# Amphenol_ICC_1.net
KiCad netlist of a schematic drawn in Altium Designer
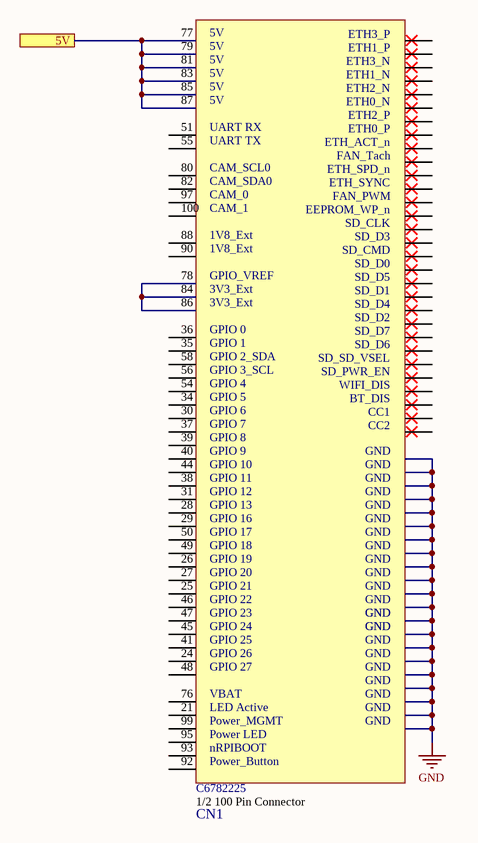
[diagram p0: Amphenol ICC_1.SchDoc]

(export (version "E")
  (design (tool "Eeschema 10.0.6"))
  (components
    (comp (ref "CN1")
      (value "1/2 100 Pin Connector")
      (footprint "CONN-SMD_100P-P0.40_10164227-1001A1RLF")
      (description "100 Position Board to Board Connector Surface Mount,P=0.4mm Gold")
      (fields (field (name "SOURCE") "LCSC"))
      (libsource (lib "C6782225_Part 1") (part "10164227-1001A1RLF"))
    )
  )
  (nets
    (net (code "1") (name "/5V") (class "Default")
      (node (ref "CN1") (pin "77") (pinfunction "77_77") (pintype "passive"))
      (node (ref "CN1") (pin "79") (pinfunction "79_79") (pintype "passive"))
      (node (ref "CN1") (pin "81") (pinfunction "81_81") (pintype "passive"))
      (node (ref "CN1") (pin "83") (pinfunction "83_83") (pintype "passive"))
      (node (ref "CN1") (pin "85") (pinfunction "85_85") (pintype "passive"))
      (node (ref "CN1") (pin "87") (pinfunction "87_87") (pintype "passive"))
    )
    (net (code "2") (name "GND") (class "Default")
      (node (ref "CN1") (pin "1") (pinfunction "1_1") (pintype "passive"))
      (node (ref "CN1") (pin "13") (pinfunction "13_13") (pintype "passive"))
      (node (ref "CN1") (pin "14") (pinfunction "14_14") (pintype "passive"))
      (node (ref "CN1") (pin "2") (pinfunction "2_2") (pintype "passive"))
      (node (ref "CN1") (pin "22") (pinfunction "22_22") (pintype "passive"))
      (node (ref "CN1") (pin "23") (pinfunction "23_23") (pintype "passive"))
      (node (ref "CN1") (pin "32") (pinfunction "32_32") (pintype "passive"))
      (node (ref "CN1") (pin "33") (pinfunction "33_33") (pintype "passive"))
      (node (ref "CN1") (pin "42") (pinfunction "42_42") (pintype "passive"))
      (node (ref "CN1") (pin "43") (pinfunction "43_43") (pintype "passive"))
      (node (ref "CN1") (pin "52") (pinfunction "52_52") (pintype "passive"))
      (node (ref "CN1") (pin "53") (pinfunction "53_53") (pintype "passive"))
      (node (ref "CN1") (pin "59") (pinfunction "59_59") (pintype "passive"))
      (node (ref "CN1") (pin "60") (pinfunction "60_60") (pintype "passive"))
      (node (ref "CN1") (pin "65") (pinfunction "65_65") (pintype "passive"))
      (node (ref "CN1") (pin "66") (pinfunction "66_66") (pintype "passive"))
      (node (ref "CN1") (pin "7") (pinfunction "7_7") (pintype "passive"))
      (node (ref "CN1") (pin "71") (pinfunction "71_71") (pintype "passive"))
      (node (ref "CN1") (pin "74") (pinfunction "74_74") (pintype "passive"))
      (node (ref "CN1") (pin "8") (pinfunction "8_8") (pintype "passive"))
      (node (ref "CN1") (pin "98") (pinfunction "98_98") (pintype "passive"))
    )
    (net (code "3") (name "Net-(CN1-GPIO_VREF)") (class "Default")
      (node (ref "CN1") (pin "78") (pinfunction "GPIO_VREF_78") (pintype "passive"))
      (node (ref "CN1") (pin "84") (pinfunction "84_84") (pintype "passive"))
      (node (ref "CN1") (pin "86") (pinfunction "86_86") (pintype "passive"))
    )
    (net (code "4") (name "unconnected-(CN1-3-PadETH_3P)") (class "Default")
      (node (ref "CN1") (pin "ETH_3P") (pinfunction "3_ETH_3P") (pintype "passive"))
    )
    (net (code "5") (name "unconnected-(CN1-4-PadETH_1P)") (class "Default")
      (node (ref "CN1") (pin "ETH_1P") (pinfunction "4_ETH_1P") (pintype "passive"))
    )
    (net (code "6") (name "unconnected-(CN1-5-PadETH_3N)") (class "Default")
      (node (ref "CN1") (pin "ETH_3N") (pinfunction "5_ETH_3N") (pintype "passive"))
    )
    (net (code "7") (name "unconnected-(CN1-6-PadETH_1N)") (class "Default")
      (node (ref "CN1") (pin "ETH_1N") (pinfunction "6_ETH_1N") (pintype "passive"))
    )
    (net (code "8") (name "unconnected-(CN1-9-PadETH_2N)") (class "Default")
      (node (ref "CN1") (pin "ETH_2N") (pinfunction "9_ETH_2N") (pintype "passive"))
    )
    (net (code "9") (name "unconnected-(CN1-10-PadETH_0N)") (class "Default")
      (node (ref "CN1") (pin "ETH_0N") (pinfunction "10_ETH_0N") (pintype "passive"))
    )
    (net (code "10") (name "unconnected-(CN1-11-PadETH_2P)") (class "Default")
      (node (ref "CN1") (pin "ETH_2P") (pinfunction "11_ETH_2P") (pintype "passive"))
    )
    (net (code "11") (name "unconnected-(CN1-12-PadETH_0N)") (class "Default")
      (node (ref "CN1") (pin "ETH_0N") (pinfunction "12_ETH_0N") (pintype "passive"))
    )
    (net (code "12") (name "unconnected-(CN1-15-PadETH_LED_3)") (class "Default")
      (node (ref "CN1") (pin "ETH_LED_3") (pinfunction "15_ETH_LED_3") (pintype "passive"))
    )
    (net (code "13") (name "unconnected-(CN1-16-PadFAN_Tacho)") (class "Default")
      (node (ref "CN1") (pin "FAN_Tacho") (pinfunction "16_FAN_Tacho") (pintype "passive"))
    )
    (net (code "14") (name "unconnected-(CN1-17-PadETH_LED_2)") (class "Default")
      (node (ref "CN1") (pin "ETH_LED_2") (pinfunction "17_ETH_LED_2") (pintype "passive"))
    )
    (net (code "15") (name "unconnected-(CN1-18-PadETH_SYNC_OUT)") (class "Default")
      (node (ref "CN1") (pin "ETH_SYNC_OUT") (pinfunction "18_ETH_SYNC_OUT") (pintype "passive"))
    )
    (net (code "16") (name "unconnected-(CN1-19-PadFAN_PWM)") (class "Default")
      (node (ref "CN1") (pin "FAN_PWM") (pinfunction "19_FAN_PWM") (pintype "passive"))
    )
    (net (code "17") (name "unconnected-(CN1-20-PadEEPROM)") (class "Default")
      (node (ref "CN1") (pin "EEPROM") (pinfunction "20_EEPROM") (pintype "passive"))
    )
    (net (code "18") (name "unconnected-(CN1-Pad21)") (class "Default")
      (node (ref "CN1") (pin "21") (pinfunction "21_21") (pintype "passive"))
    )
    (net (code "19") (name "unconnected-(CN1-Pad24)") (class "Default")
      (node (ref "CN1") (pin "24") (pinfunction "24_24") (pintype "passive"))
    )
    (net (code "20") (name "unconnected-(CN1-Pad25)") (class "Default")
      (node (ref "CN1") (pin "25") (pinfunction "25_25") (pintype "passive"))
    )
    (net (code "21") (name "unconnected-(CN1-Pad26)") (class "Default")
      (node (ref "CN1") (pin "26") (pinfunction "26_26") (pintype "passive"))
    )
    (net (code "22") (name "unconnected-(CN1-Pad27)") (class "Default")
      (node (ref "CN1") (pin "27") (pinfunction "27_27") (pintype "passive"))
    )
    (net (code "23") (name "unconnected-(CN1-Pad28)") (class "Default")
      (node (ref "CN1") (pin "28") (pinfunction "28_28") (pintype "passive"))
    )
    (net (code "24") (name "unconnected-(CN1-Pad29)") (class "Default")
      (node (ref "CN1") (pin "29") (pinfunction "29_29") (pintype "passive"))
    )
    (net (code "25") (name "unconnected-(CN1-Pad30)") (class "Default")
      (node (ref "CN1") (pin "30") (pinfunction "30_30") (pintype "passive"))
    )
    (net (code "26") (name "unconnected-(CN1-Pad31)") (class "Default")
      (node (ref "CN1") (pin "31") (pinfunction "31_31") (pintype "passive"))
    )
    (net (code "27") (name "unconnected-(CN1-Pad34)") (class "Default")
      (node (ref "CN1") (pin "34") (pinfunction "34_34") (pintype "passive"))
    )
    (net (code "28") (name "unconnected-(CN1-Pad35)") (class "Default")
      (node (ref "CN1") (pin "35") (pinfunction "35_35") (pintype "passive"))
    )
    (net (code "29") (name "unconnected-(CN1-Pad36)") (class "Default")
      (node (ref "CN1") (pin "36") (pinfunction "36_36") (pintype "passive"))
    )
    (net (code "30") (name "unconnected-(CN1-Pad37)") (class "Default")
      (node (ref "CN1") (pin "37") (pinfunction "37_37") (pintype "passive"))
    )
    (net (code "31") (name "unconnected-(CN1-Pad38)") (class "Default")
      (node (ref "CN1") (pin "38") (pinfunction "38_38") (pintype "passive"))
    )
    (net (code "32") (name "unconnected-(CN1-Pad39)") (class "Default")
      (node (ref "CN1") (pin "39") (pinfunction "39_39") (pintype "passive"))
    )
    (net (code "33") (name "unconnected-(CN1-Pad40)") (class "Default")
      (node (ref "CN1") (pin "40") (pinfunction "40_40") (pintype "passive"))
    )
    (net (code "34") (name "unconnected-(CN1-Pad41)") (class "Default")
      (node (ref "CN1") (pin "41") (pinfunction "41_41") (pintype "passive"))
    )
    (net (code "35") (name "unconnected-(CN1-Pad44)") (class "Default")
      (node (ref "CN1") (pin "44") (pinfunction "44_44") (pintype "passive"))
    )
    (net (code "36") (name "unconnected-(CN1-Pad45)") (class "Default")
      (node (ref "CN1") (pin "45") (pinfunction "45_45") (pintype "passive"))
    )
    (net (code "37") (name "unconnected-(CN1-Pad46)") (class "Default")
      (node (ref "CN1") (pin "46") (pinfunction "46_46") (pintype "passive"))
    )
    (net (code "38") (name "unconnected-(CN1-Pad47)") (class "Default")
      (node (ref "CN1") (pin "47") (pinfunction "47_47") (pintype "passive"))
    )
    (net (code "39") (name "unconnected-(CN1-Pad48)") (class "Default")
      (node (ref "CN1") (pin "48") (pinfunction "48_48") (pintype "passive"))
    )
    (net (code "40") (name "unconnected-(CN1-Pad49)") (class "Default")
      (node (ref "CN1") (pin "49") (pinfunction "49_49") (pintype "passive"))
    )
    (net (code "41") (name "unconnected-(CN1-Pad50)") (class "Default")
      (node (ref "CN1") (pin "50") (pinfunction "50_50") (pintype "passive"))
    )
    (net (code "42") (name "unconnected-(CN1-Pad51)") (class "Default")
      (node (ref "CN1") (pin "51") (pinfunction "51_51") (pintype "passive"))
    )
    (net (code "43") (name "unconnected-(CN1-Pad54)") (class "Default")
      (node (ref "CN1") (pin "54") (pinfunction "54_54") (pintype "passive"))
    )
    (net (code "44") (name "unconnected-(CN1-Pad55)") (class "Default")
      (node (ref "CN1") (pin "55") (pinfunction "55_55") (pintype "passive"))
    )
    (net (code "45") (name "unconnected-(CN1-Pad56)") (class "Default")
      (node (ref "CN1") (pin "56") (pinfunction "56_56") (pintype "passive"))
    )
    (net (code "46") (name "unconnected-(CN1-Pad57)") (class "Default")
      (node (ref "CN1") (pin "57") (pinfunction "57_57") (pintype "passive"))
    )
    (net (code "47") (name "unconnected-(CN1-Pad58)") (class "Default")
      (node (ref "CN1") (pin "58") (pinfunction "58_58") (pintype "passive"))
    )
    (net (code "48") (name "unconnected-(CN1-Pad61)") (class "Default")
      (node (ref "CN1") (pin "61") (pinfunction "61_61") (pintype "passive"))
    )
    (net (code "49") (name "unconnected-(CN1-Pad62)") (class "Default")
      (node (ref "CN1") (pin "62") (pinfunction "62_62") (pintype "passive"))
    )
    (net (code "50") (name "unconnected-(CN1-Pad63)") (class "Default")
      (node (ref "CN1") (pin "63") (pinfunction "63_63") (pintype "passive"))
    )
    (net (code "51") (name "unconnected-(CN1-Pad64)") (class "Default")
      (node (ref "CN1") (pin "64") (pinfunction "64_64") (pintype "passive"))
    )
    (net (code "52") (name "unconnected-(CN1-Pad67)") (class "Default")
      (node (ref "CN1") (pin "67") (pinfunction "67_67") (pintype "passive"))
    )
    (net (code "53") (name "unconnected-(CN1-Pad68)") (class "Default")
      (node (ref "CN1") (pin "68") (pinfunction "68_68") (pintype "passive"))
    )
    (net (code "54") (name "unconnected-(CN1-Pad69)") (class "Default")
      (node (ref "CN1") (pin "69") (pinfunction "69_69") (pintype "passive"))
    )
    (net (code "55") (name "unconnected-(CN1-Pad70)") (class "Default")
      (node (ref "CN1") (pin "70") (pinfunction "70_70") (pintype "passive"))
    )
    (net (code "56") (name "unconnected-(CN1-Pad72)") (class "Default")
      (node (ref "CN1") (pin "72") (pinfunction "72_72") (pintype "passive"))
    )
    (net (code "57") (name "unconnected-(CN1-Pad73)") (class "Default")
      (node (ref "CN1") (pin "73") (pinfunction "73_73") (pintype "passive"))
    )
    (net (code "58") (name "unconnected-(CN1-Pad75)") (class "Default")
      (node (ref "CN1") (pin "75") (pinfunction "75_75") (pintype "passive"))
    )
    (net (code "59") (name "unconnected-(CN1-Pad76)") (class "Default")
      (node (ref "CN1") (pin "76") (pinfunction "76_76") (pintype "passive"))
    )
    (net (code "60") (name "unconnected-(CN1-Pad80)") (class "Default")
      (node (ref "CN1") (pin "80") (pinfunction "80_80") (pintype "passive"))
    )
    (net (code "61") (name "unconnected-(CN1-Pad82)") (class "Default")
      (node (ref "CN1") (pin "82") (pinfunction "82_82") (pintype "passive"))
    )
    (net (code "62") (name "unconnected-(CN1-Pad88)") (class "Default")
      (node (ref "CN1") (pin "88") (pinfunction "88_88") (pintype "passive"))
    )
    (net (code "63") (name "unconnected-(CN1-Pad89)") (class "Default")
      (node (ref "CN1") (pin "89") (pinfunction "89_89") (pintype "passive"))
    )
    (net (code "64") (name "unconnected-(CN1-Pad90)") (class "Default")
      (node (ref "CN1") (pin "90") (pinfunction "90_90") (pintype "passive"))
    )
    (net (code "65") (name "unconnected-(CN1-Pad91)") (class "Default")
      (node (ref "CN1") (pin "91") (pinfunction "91_91") (pintype "passive"))
    )
    (net (code "66") (name "unconnected-(CN1-Pad92)") (class "Default")
      (node (ref "CN1") (pin "92") (pinfunction "92_92") (pintype "passive"))
    )
    (net (code "67") (name "unconnected-(CN1-Pad93)") (class "Default")
      (node (ref "CN1") (pin "93") (pinfunction "93_93") (pintype "passive"))
    )
    (net (code "68") (name "unconnected-(CN1-Pad94)") (class "Default")
      (node (ref "CN1") (pin "94") (pinfunction "94_94") (pintype "passive"))
    )
    (net (code "69") (name "unconnected-(CN1-Pad95)") (class "Default")
      (node (ref "CN1") (pin "95") (pinfunction "95_95") (pintype "passive"))
    )
    (net (code "70") (name "unconnected-(CN1-Pad96)") (class "Default")
      (node (ref "CN1") (pin "96") (pinfunction "96_96") (pintype "passive"))
    )
    (net (code "71") (name "unconnected-(CN1-Pad97)") (class "Default")
      (node (ref "CN1") (pin "97") (pinfunction "97_97") (pintype "passive"))
    )
    (net (code "72") (name "unconnected-(CN1-Pad99)") (class "Default")
      (node (ref "CN1") (pin "99") (pinfunction "99_99") (pintype "passive"))
    )
    (net (code "73") (name "unconnected-(CN1-Pad100)") (class "Default")
      (node (ref "CN1") (pin "100") (pinfunction "100_100") (pintype "passive"))
    )
  )
)
